# Educational-BoosterPack-RevA1-schematic.net
KiCad netlist of a schematic drawn in EAGLE
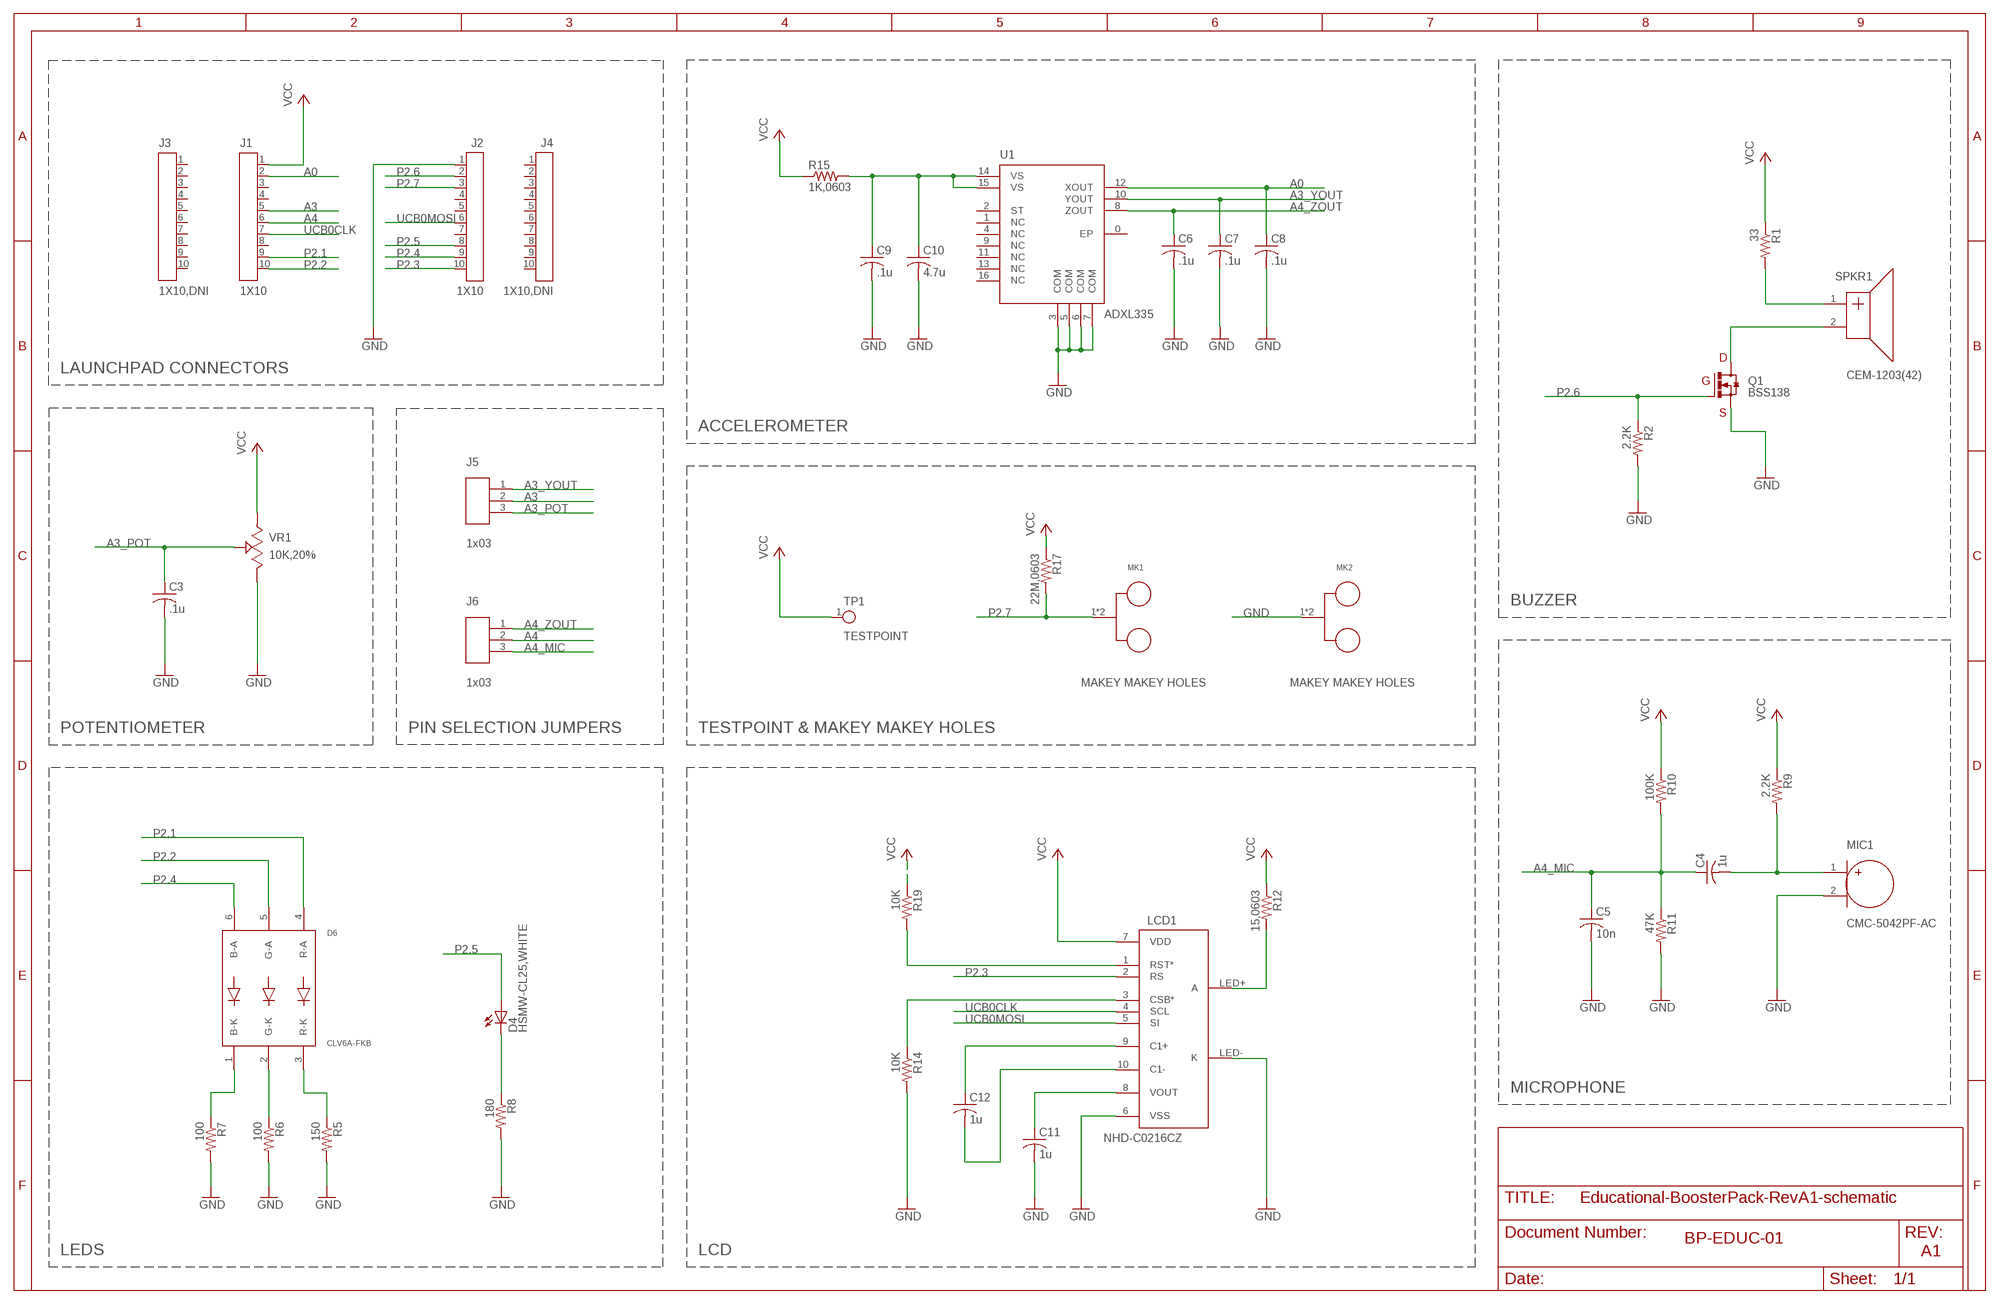
[diagram p0: schematic, sheet 1]

(export (version "E")
  (design (tool "Eeschema 10.0.6"))
  (components
    (comp (ref "C3")
      (value ".1u")
      (footprint "eagle-import:C0402")
      (libsource (lib "eagle-import") (part "C-USC0402"))
    )
    (comp (ref "C4")
      (value "1u")
      (footprint "eagle-import:C0402")
      (libsource (lib "eagle-import") (part "C-USC0402"))
    )
    (comp (ref "C5")
      (value "10n")
      (footprint "eagle-import:C0402")
      (libsource (lib "eagle-import") (part "C-USC0402"))
    )
    (comp (ref "C6")
      (value ".1u")
      (footprint "eagle-import:C0402")
      (libsource (lib "eagle-import") (part "C-USC0402"))
    )
    (comp (ref "C7")
      (value ".1u")
      (footprint "eagle-import:C0402")
      (libsource (lib "eagle-import") (part "C-USC0402"))
    )
    (comp (ref "C8")
      (value ".1u")
      (footprint "eagle-import:C0402")
      (libsource (lib "eagle-import") (part "C-USC0402"))
    )
    (comp (ref "C9")
      (value ".1u")
      (footprint "eagle-import:C0402")
      (libsource (lib "eagle-import") (part "C-USC0402"))
    )
    (comp (ref "C10")
      (value "4.7u")
      (footprint "eagle-import:C0603")
      (libsource (lib "eagle-import") (part "C-USC0603"))
    )
    (comp (ref "C11")
      (value "1u")
      (footprint "eagle-import:C0402")
      (libsource (lib "eagle-import") (part "C-USC0402"))
    )
    (comp (ref "C12")
      (value "1u")
      (footprint "eagle-import:C0402")
      (libsource (lib "eagle-import") (part "C-USC0402"))
    )
    (comp (ref "D4")
      (value "HSMW-CL25,WHITE")
      (footprint "eagle-import:CHIPLED_0603")
      (libsource (lib "eagle-import") (part "LEDCHIPLED_0603"))
    )
    (comp (ref "D6")
      (value "CLV6A-FKB")
      (footprint "eagle-import:TRICOLOR-LED6")
      (libsource (lib "eagle-import") (part "CLV6A-FKB"))
    )
    (comp (ref "J1")
      (value "1X10")
      (footprint "eagle-import:1X10")
      (libsource (lib "eagle-import") (part "HEADER1X10"))
    )
    (comp (ref "J2")
      (value "1X10")
      (footprint "eagle-import:1X10")
      (libsource (lib "eagle-import") (part "HEADER1X10"))
    )
    (comp (ref "J3")
      (value "1X10,DNI")
      (footprint "eagle-import:1X10")
      (libsource (lib "eagle-import") (part "HEADER1X10"))
    )
    (comp (ref "J4")
      (value "1X10,DNI")
      (footprint "eagle-import:1X10")
      (libsource (lib "eagle-import") (part "HEADER1X10"))
    )
    (comp (ref "J5")
      (value "1x03")
      (footprint "eagle-import:1X03")
      (libsource (lib "eagle-import") (part "HEADER1X03"))
    )
    (comp (ref "J6")
      (value "1x03")
      (footprint "eagle-import:1X03")
      (libsource (lib "eagle-import") (part "HEADER1X03"))
    )
    (comp (ref "LCD1")
      (value "NHD-C0216CZ")
      (footprint "eagle-import:GENERIC-LCD10-2")
      (libsource (lib "eagle-import") (part "NHD-C0216CZ"))
    )
    (comp (ref "MIC1")
      (value "CMC-5042PF-AC")
      (footprint "eagle-import:GENERIC-2PADS2")
      (libsource (lib "eagle-import") (part "CMC-5042PF-AC"))
    )
    (comp (ref "MK1")
      (value "MAKEYMAKEY")
      (footprint "eagle-import:MAKEYMAKEY")
      (libsource (lib "eagle-import") (part "MAKEYMAKEY"))
    )
    (comp (ref "MK2")
      (value "MAKEYMAKEY")
      (footprint "eagle-import:MAKEYMAKEY")
      (libsource (lib "eagle-import") (part "MAKEYMAKEY"))
    )
    (comp (ref "Q1")
      (value "BSS138")
      (footprint "eagle-import:SOT23-3")
      (libsource (lib "eagle-import") (part "BSS138"))
    )
    (comp (ref "R1")
      (value "33")
      (footprint "eagle-import:R0402")
      (libsource (lib "eagle-import") (part "R-US_R0402"))
    )
    (comp (ref "R2")
      (value "2.2K")
      (footprint "eagle-import:R0402")
      (libsource (lib "eagle-import") (part "R-US_R0402"))
    )
    (comp (ref "R5")
      (value "150")
      (footprint "eagle-import:R0402")
      (libsource (lib "eagle-import") (part "R-US_R0402"))
    )
    (comp (ref "R6")
      (value "100")
      (footprint "eagle-import:R0402")
      (libsource (lib "eagle-import") (part "R-US_R0402"))
    )
    (comp (ref "R7")
      (value "100")
      (footprint "eagle-import:R0402")
      (libsource (lib "eagle-import") (part "R-US_R0402"))
    )
    (comp (ref "R8")
      (value "180")
      (footprint "eagle-import:R0402")
      (libsource (lib "eagle-import") (part "R-US_R0402"))
    )
    (comp (ref "R9")
      (value "2.2K")
      (footprint "eagle-import:R0402")
      (libsource (lib "eagle-import") (part "R-US_R0402"))
    )
    (comp (ref "R10")
      (value "100K")
      (footprint "eagle-import:R0402")
      (libsource (lib "eagle-import") (part "R-US_R0402"))
    )
    (comp (ref "R11")
      (value "47K")
      (footprint "eagle-import:R0402")
      (libsource (lib "eagle-import") (part "R-US_R0402"))
    )
    (comp (ref "R12")
      (value "15,0603")
      (footprint "eagle-import:R0603")
      (libsource (lib "eagle-import") (part "R-US_R0603"))
    )
    (comp (ref "R14")
      (value "10K")
      (footprint "eagle-import:R0402")
      (libsource (lib "eagle-import") (part "R-US_R0402"))
    )
    (comp (ref "R15")
      (value "1K,0603")
      (footprint "eagle-import:R0603")
      (libsource (lib "eagle-import") (part "R-US_R0603"))
    )
    (comp (ref "R17")
      (value "22M,0603")
      (footprint "eagle-import:R0603")
      (libsource (lib "eagle-import") (part "R-US_R0603"))
    )
    (comp (ref "R19")
      (value "10K")
      (footprint "eagle-import:R0402")
      (libsource (lib "eagle-import") (part "R-US_R0402"))
    )
    (comp (ref "SPKR1")
      (value "CEM-1203(42)")
      (footprint "eagle-import:GENERIC-2PADS")
      (libsource (lib "eagle-import") (part "CEM-1203(42)"))
    )
    (comp (ref "TP1")
      (value "TESTPOINT")
      (footprint "eagle-import:TESTPOINT")
      (libsource (lib "eagle-import") (part "TESTPOINT"))
    )
    (comp (ref "U1")
      (value "ADXL335")
      (footprint "eagle-import:LFCSP-16")
      (libsource (lib "eagle-import") (part "ADXL335"))
    )
    (comp (ref "VR1")
      (value "10K,20%")
      (footprint "eagle-import:GENERIC-3HOLES")
      (libsource (lib "eagle-import") (part "3352T"))
    )
  )
  (nets
    (net (code "1") (name "/A0") (class "Default")
      (node (ref "C8") (pin "1") (pinfunction "1_1") (pintype "passive"))
      (node (ref "J1") (pin "2") (pinfunction "2_2") (pintype "bidirectional"))
      (node (ref "U1") (pin "12") (pinfunction "XOUT_12") (pintype "output"))
    )
    (net (code "2") (name "/A3") (class "Default")
      (node (ref "J1") (pin "5") (pinfunction "5_5") (pintype "bidirectional"))
      (node (ref "J5") (pin "2") (pinfunction "2_2") (pintype "bidirectional"))
    )
    (net (code "3") (name "/A3_POT") (class "Default")
      (node (ref "C3") (pin "1") (pinfunction "1_1") (pintype "passive"))
      (node (ref "J5") (pin "3") (pinfunction "3_3") (pintype "bidirectional"))
      (node (ref "VR1") (pin "2") (pinfunction "2_2") (pintype "passive"))
    )
    (net (code "4") (name "/A3_YOUT") (class "Default")
      (node (ref "C7") (pin "1") (pinfunction "1_1") (pintype "passive"))
      (node (ref "J5") (pin "1") (pinfunction "1_1") (pintype "bidirectional"))
      (node (ref "U1") (pin "10") (pinfunction "YOUT_10") (pintype "output"))
    )
    (net (code "5") (name "/A4") (class "Default")
      (node (ref "J1") (pin "6") (pinfunction "6_6") (pintype "bidirectional"))
      (node (ref "J6") (pin "2") (pinfunction "2_2") (pintype "bidirectional"))
    )
    (net (code "6") (name "/A4_MIC") (class "Default")
      (node (ref "C4") (pin "1") (pinfunction "1_1") (pintype "passive"))
      (node (ref "C5") (pin "1") (pinfunction "1_1") (pintype "passive"))
      (node (ref "J6") (pin "3") (pinfunction "3_3") (pintype "bidirectional"))
      (node (ref "R10") (pin "2") (pinfunction "2_2") (pintype "passive"))
      (node (ref "R11") (pin "1") (pinfunction "1_1") (pintype "passive"))
    )
    (net (code "7") (name "/A4_ZOUT") (class "Default")
      (node (ref "C6") (pin "1") (pinfunction "1_1") (pintype "passive"))
      (node (ref "J6") (pin "1") (pinfunction "1_1") (pintype "bidirectional"))
      (node (ref "U1") (pin "8") (pinfunction "ZOUT_8") (pintype "output"))
    )
    (net (code "8") (name "/P2.1") (class "Default")
      (node (ref "D6") (pin "4") (pinfunction "R-A_4") (pintype "bidirectional"))
      (node (ref "J1") (pin "9") (pinfunction "9_9") (pintype "bidirectional"))
    )
    (net (code "9") (name "/P2.2") (class "Default")
      (node (ref "D6") (pin "5") (pinfunction "G-A_5") (pintype "bidirectional"))
      (node (ref "J1") (pin "10") (pinfunction "10_10") (pintype "bidirectional"))
    )
    (net (code "10") (name "/P2.3") (class "Default")
      (node (ref "J2") (pin "10") (pinfunction "10_10") (pintype "bidirectional"))
      (node (ref "LCD1") (pin "2") (pinfunction "RS_2") (pintype "input"))
    )
    (net (code "11") (name "/P2.4") (class "Default")
      (node (ref "D6") (pin "6") (pinfunction "B-A_6") (pintype "bidirectional"))
      (node (ref "J2") (pin "9") (pinfunction "9_9") (pintype "bidirectional"))
    )
    (net (code "12") (name "/P2.5") (class "Default")
      (node (ref "D4") (pin "A") (pinfunction "A_A") (pintype "passive"))
      (node (ref "J2") (pin "8") (pinfunction "8_8") (pintype "bidirectional"))
    )
    (net (code "13") (name "/P2.6") (class "Default")
      (node (ref "J2") (pin "2") (pinfunction "2_2") (pintype "bidirectional"))
      (node (ref "Q1") (pin "1") (pinfunction "G_1") (pintype "passive"))
      (node (ref "R2") (pin "1") (pinfunction "1_1") (pintype "passive"))
    )
    (net (code "14") (name "/P2.7") (class "Default")
      (node (ref "J2") (pin "3") (pinfunction "3_3") (pintype "bidirectional"))
      (node (ref "MK1") (pin "1") (pinfunction "P$1_1") (pintype "bidirectional"))
      (node (ref "MK1") (pin "2") (pinfunction "P$1_2") (pintype "bidirectional"))
      (node (ref "R17") (pin "2") (pinfunction "2_2") (pintype "passive"))
    )
    (net (code "15") (name "/UCB0CLK") (class "Default")
      (node (ref "J1") (pin "7") (pinfunction "7_7") (pintype "bidirectional"))
      (node (ref "LCD1") (pin "4") (pinfunction "SCL_4") (pintype "input"))
    )
    (net (code "16") (name "/UCB0MOSI") (class "Default")
      (node (ref "J2") (pin "6") (pinfunction "6_6") (pintype "bidirectional"))
      (node (ref "LCD1") (pin "5") (pinfunction "SI_5") (pintype "input"))
    )
    (net (code "17") (name "GND") (class "Default")
      (node (ref "C10") (pin "2") (pinfunction "2_2") (pintype "passive"))
      (node (ref "C11") (pin "2") (pinfunction "2_2") (pintype "passive"))
      (node (ref "C3") (pin "2") (pinfunction "2_2") (pintype "passive"))
      (node (ref "C5") (pin "2") (pinfunction "2_2") (pintype "passive"))
      (node (ref "C6") (pin "2") (pinfunction "2_2") (pintype "passive"))
      (node (ref "C7") (pin "2") (pinfunction "2_2") (pintype "passive"))
      (node (ref "C8") (pin "2") (pinfunction "2_2") (pintype "passive"))
      (node (ref "C9") (pin "2") (pinfunction "2_2") (pintype "passive"))
      (node (ref "J2") (pin "1") (pinfunction "1_1") (pintype "bidirectional"))
      (node (ref "LCD1") (pin "6") (pinfunction "VSS_6") (pintype "power_in"))
      (node (ref "LCD1") (pin "LED-") (pinfunction "K_LED-") (pintype "power_in"))
      (node (ref "MIC1") (pin "2") (pinfunction "MIC_N_2") (pintype "passive"))
      (node (ref "MK2") (pin "1") (pinfunction "P$1_1") (pintype "bidirectional"))
      (node (ref "MK2") (pin "2") (pinfunction "P$1_2") (pintype "bidirectional"))
      (node (ref "Q1") (pin "2") (pinfunction "S_2") (pintype "passive"))
      (node (ref "R11") (pin "2") (pinfunction "2_2") (pintype "passive"))
      (node (ref "R14") (pin "2") (pinfunction "2_2") (pintype "passive"))
      (node (ref "R2") (pin "2") (pinfunction "2_2") (pintype "passive"))
      (node (ref "R5") (pin "2") (pinfunction "2_2") (pintype "passive"))
      (node (ref "R6") (pin "2") (pinfunction "2_2") (pintype "passive"))
      (node (ref "R7") (pin "2") (pinfunction "2_2") (pintype "passive"))
      (node (ref "R8") (pin "2") (pinfunction "2_2") (pintype "passive"))
      (node (ref "U1") (pin "3") (pinfunction "COM_3") (pintype "power_in"))
      (node (ref "U1") (pin "5") (pinfunction "COM_5") (pintype "power_in"))
      (node (ref "U1") (pin "6") (pinfunction "COM_6") (pintype "power_in"))
      (node (ref "U1") (pin "7") (pinfunction "COM_7") (pintype "power_in"))
      (node (ref "VR1") (pin "3") (pinfunction "3_3") (pintype "passive"))
    )
    (net (code "18") (name "Net-(C10-Pad1)") (class "Default")
      (node (ref "C10") (pin "1") (pinfunction "1_1") (pintype "passive"))
      (node (ref "C9") (pin "1") (pinfunction "1_1") (pintype "passive"))
      (node (ref "R15") (pin "2") (pinfunction "2_2") (pintype "passive"))
      (node (ref "U1") (pin "14") (pinfunction "VS_14") (pintype "power_in"))
      (node (ref "U1") (pin "15") (pinfunction "VS_15") (pintype "power_in"))
    )
    (net (code "19") (name "Net-(D4-PadC)") (class "Default")
      (node (ref "D4") (pin "C") (pinfunction "C_C") (pintype "passive"))
      (node (ref "R8") (pin "1") (pinfunction "1_1") (pintype "passive"))
    )
    (net (code "20") (name "Net-(D6-B-K)") (class "Default")
      (node (ref "D6") (pin "1") (pinfunction "B-K_1") (pintype "bidirectional"))
      (node (ref "R7") (pin "1") (pinfunction "1_1") (pintype "passive"))
    )
    (net (code "21") (name "Net-(D6-G-K)") (class "Default")
      (node (ref "D6") (pin "2") (pinfunction "G-K_2") (pintype "bidirectional"))
      (node (ref "R6") (pin "1") (pinfunction "1_1") (pintype "passive"))
    )
    (net (code "22") (name "Net-(D6-R-K)") (class "Default")
      (node (ref "D6") (pin "3") (pinfunction "R-K_3") (pintype "bidirectional"))
      (node (ref "R5") (pin "1") (pinfunction "1_1") (pintype "passive"))
    )
    (net (code "23") (name "Net-(LCD1-A)") (class "Default")
      (node (ref "LCD1") (pin "LED+") (pinfunction "A_LED+") (pintype "power_in"))
      (node (ref "R12") (pin "2") (pinfunction "2_2") (pintype "passive"))
    )
    (net (code "24") (name "Net-(LCD1-C1+)") (class "Default")
      (node (ref "C12") (pin "1") (pinfunction "1_1") (pintype "passive"))
      (node (ref "LCD1") (pin "9") (pinfunction "C1+_9") (pintype "power_in"))
    )
    (net (code "25") (name "Net-(LCD1-C1-)") (class "Default")
      (node (ref "C12") (pin "2") (pinfunction "2_2") (pintype "passive"))
      (node (ref "LCD1") (pin "10") (pinfunction "C1-_10") (pintype "power_in"))
    )
    (net (code "26") (name "Net-(LCD1-CSB*)") (class "Default")
      (node (ref "LCD1") (pin "3") (pinfunction "CSB*_3") (pintype "input"))
      (node (ref "R14") (pin "1") (pinfunction "1_1") (pintype "passive"))
    )
    (net (code "27") (name "Net-(LCD1-RST*)") (class "Default")
      (node (ref "LCD1") (pin "1") (pinfunction "RST*_1") (pintype "input"))
      (node (ref "R19") (pin "2") (pinfunction "2_2") (pintype "passive"))
    )
    (net (code "28") (name "Net-(LCD1-VOUT)") (class "Default")
      (node (ref "C11") (pin "1") (pinfunction "1_1") (pintype "passive"))
      (node (ref "LCD1") (pin "8") (pinfunction "VOUT_8") (pintype "power_in"))
    )
    (net (code "29") (name "Net-(MIC1-MIC_P)") (class "Default")
      (node (ref "C4") (pin "2") (pinfunction "2_2") (pintype "passive"))
      (node (ref "MIC1") (pin "1") (pinfunction "MIC_P_1") (pintype "passive"))
      (node (ref "R9") (pin "2") (pinfunction "2_2") (pintype "passive"))
    )
    (net (code "30") (name "Net-(Q1-D)") (class "Default")
      (node (ref "Q1") (pin "3") (pinfunction "D_3") (pintype "passive"))
      (node (ref "SPKR1") (pin "2") (pinfunction "SPKR_N_2") (pintype "passive"))
    )
    (net (code "31") (name "Net-(SPKR1-SPKR_P)") (class "Default")
      (node (ref "R1") (pin "2") (pinfunction "2_2") (pintype "passive"))
      (node (ref "SPKR1") (pin "1") (pinfunction "SPKR_P_1") (pintype "passive"))
    )
    (net (code "32") (name "VCC") (class "Default")
      (node (ref "J1") (pin "1") (pinfunction "1_1") (pintype "bidirectional"))
      (node (ref "LCD1") (pin "7") (pinfunction "VDD_7") (pintype "power_in"))
      (node (ref "R1") (pin "1") (pinfunction "1_1") (pintype "passive"))
      (node (ref "R10") (pin "1") (pinfunction "1_1") (pintype "passive"))
      (node (ref "R12") (pin "1") (pinfunction "1_1") (pintype "passive"))
      (node (ref "R15") (pin "1") (pinfunction "1_1") (pintype "passive"))
      (node (ref "R17") (pin "1") (pinfunction "1_1") (pintype "passive"))
      (node (ref "R19") (pin "1") (pinfunction "1_1") (pintype "passive"))
      (node (ref "R9") (pin "1") (pinfunction "1_1") (pintype "passive"))
      (node (ref "TP1") (pin "1") (pinfunction "P$1_1") (pintype "passive"))
      (node (ref "VR1") (pin "1") (pinfunction "1_1") (pintype "passive"))
    )
    (net (code "33") (name "unconnected-(J1-Pad3)") (class "Default")
      (node (ref "J1") (pin "3") (pinfunction "3_3") (pintype "bidirectional"))
    )
    (net (code "34") (name "unconnected-(J1-Pad4)") (class "Default")
      (node (ref "J1") (pin "4") (pinfunction "4_4") (pintype "bidirectional"))
    )
    (net (code "35") (name "unconnected-(J1-Pad8)") (class "Default")
      (node (ref "J1") (pin "8") (pinfunction "8_8") (pintype "bidirectional"))
    )
    (net (code "36") (name "unconnected-(J2-Pad4)") (class "Default")
      (node (ref "J2") (pin "4") (pinfunction "4_4") (pintype "bidirectional"))
    )
    (net (code "37") (name "unconnected-(J2-Pad5)") (class "Default")
      (node (ref "J2") (pin "5") (pinfunction "5_5") (pintype "bidirectional"))
    )
    (net (code "38") (name "unconnected-(J2-Pad7)") (class "Default")
      (node (ref "J2") (pin "7") (pinfunction "7_7") (pintype "bidirectional"))
    )
    (net (code "39") (name "unconnected-(J3-Pad1)") (class "Default")
      (node (ref "J3") (pin "1") (pinfunction "1_1") (pintype "bidirectional"))
    )
    (net (code "40") (name "unconnected-(J3-Pad2)") (class "Default")
      (node (ref "J3") (pin "2") (pinfunction "2_2") (pintype "bidirectional"))
    )
    (net (code "41") (name "unconnected-(J3-Pad3)") (class "Default")
      (node (ref "J3") (pin "3") (pinfunction "3_3") (pintype "bidirectional"))
    )
    (net (code "42") (name "unconnected-(J3-Pad4)") (class "Default")
      (node (ref "J3") (pin "4") (pinfunction "4_4") (pintype "bidirectional"))
    )
    (net (code "43") (name "unconnected-(J3-Pad5)") (class "Default")
      (node (ref "J3") (pin "5") (pinfunction "5_5") (pintype "bidirectional"))
    )
    (net (code "44") (name "unconnected-(J3-Pad6)") (class "Default")
      (node (ref "J3") (pin "6") (pinfunction "6_6") (pintype "bidirectional"))
    )
    (net (code "45") (name "unconnected-(J3-Pad7)") (class "Default")
      (node (ref "J3") (pin "7") (pinfunction "7_7") (pintype "bidirectional"))
    )
    (net (code "46") (name "unconnected-(J3-Pad8)") (class "Default")
      (node (ref "J3") (pin "8") (pinfunction "8_8") (pintype "bidirectional"))
    )
    (net (code "47") (name "unconnected-(J3-Pad9)") (class "Default")
      (node (ref "J3") (pin "9") (pinfunction "9_9") (pintype "bidirectional"))
    )
    (net (code "48") (name "unconnected-(J3-Pad10)") (class "Default")
      (node (ref "J3") (pin "10") (pinfunction "10_10") (pintype "bidirectional"))
    )
    (net (code "49") (name "unconnected-(J4-Pad1)") (class "Default")
      (node (ref "J4") (pin "1") (pinfunction "1_1") (pintype "bidirectional"))
    )
    (net (code "50") (name "unconnected-(J4-Pad2)") (class "Default")
      (node (ref "J4") (pin "2") (pinfunction "2_2") (pintype "bidirectional"))
    )
    (net (code "51") (name "unconnected-(J4-Pad3)") (class "Default")
      (node (ref "J4") (pin "3") (pinfunction "3_3") (pintype "bidirectional"))
    )
    (net (code "52") (name "unconnected-(J4-Pad4)") (class "Default")
      (node (ref "J4") (pin "4") (pinfunction "4_4") (pintype "bidirectional"))
    )
    (net (code "53") (name "unconnected-(J4-Pad5)") (class "Default")
      (node (ref "J4") (pin "5") (pinfunction "5_5") (pintype "bidirectional"))
    )
    (net (code "54") (name "unconnected-(J4-Pad6)") (class "Default")
      (node (ref "J4") (pin "6") (pinfunction "6_6") (pintype "bidirectional"))
    )
    (net (code "55") (name "unconnected-(J4-Pad7)") (class "Default")
      (node (ref "J4") (pin "7") (pinfunction "7_7") (pintype "bidirectional"))
    )
    (net (code "56") (name "unconnected-(J4-Pad8)") (class "Default")
      (node (ref "J4") (pin "8") (pinfunction "8_8") (pintype "bidirectional"))
    )
    (net (code "57") (name "unconnected-(J4-Pad9)") (class "Default")
      (node (ref "J4") (pin "9") (pinfunction "9_9") (pintype "bidirectional"))
    )
    (net (code "58") (name "unconnected-(J4-Pad10)") (class "Default")
      (node (ref "J4") (pin "10") (pinfunction "10_10") (pintype "bidirectional"))
    )
    (net (code "59") (name "unconnected-(U1-EP-Pad0)") (class "Default")
      (node (ref "U1") (pin "0") (pinfunction "EP_0") (pintype "bidirectional"))
    )
    (net (code "60") (name "unconnected-(U1-NC-Pad1)") (class "Default")
      (node (ref "U1") (pin "1") (pinfunction "NC_1") (pintype "bidirectional"))
    )
    (net (code "61") (name "unconnected-(U1-NC-Pad4)") (class "Default")
      (node (ref "U1") (pin "4") (pinfunction "NC_4") (pintype "bidirectional"))
    )
    (net (code "62") (name "unconnected-(U1-NC-Pad9)") (class "Default")
      (node (ref "U1") (pin "9") (pinfunction "NC_9") (pintype "bidirectional"))
    )
    (net (code "63") (name "unconnected-(U1-NC-Pad11)") (class "Default")
      (node (ref "U1") (pin "11") (pinfunction "NC_11") (pintype "bidirectional"))
    )
    (net (code "64") (name "unconnected-(U1-NC-Pad13)") (class "Default")
      (node (ref "U1") (pin "13") (pinfunction "NC_13") (pintype "bidirectional"))
    )
    (net (code "65") (name "unconnected-(U1-NC-Pad16)") (class "Default")
      (node (ref "U1") (pin "16") (pinfunction "NC_16") (pintype "bidirectional"))
    )
    (net (code "66") (name "unconnected-(U1-ST-Pad2)") (class "Default")
      (node (ref "U1") (pin "2") (pinfunction "ST_2") (pintype "input"))
    )
  )
)
